# eth.net
KiCad netlist of a schematic drawn in Altium Designer
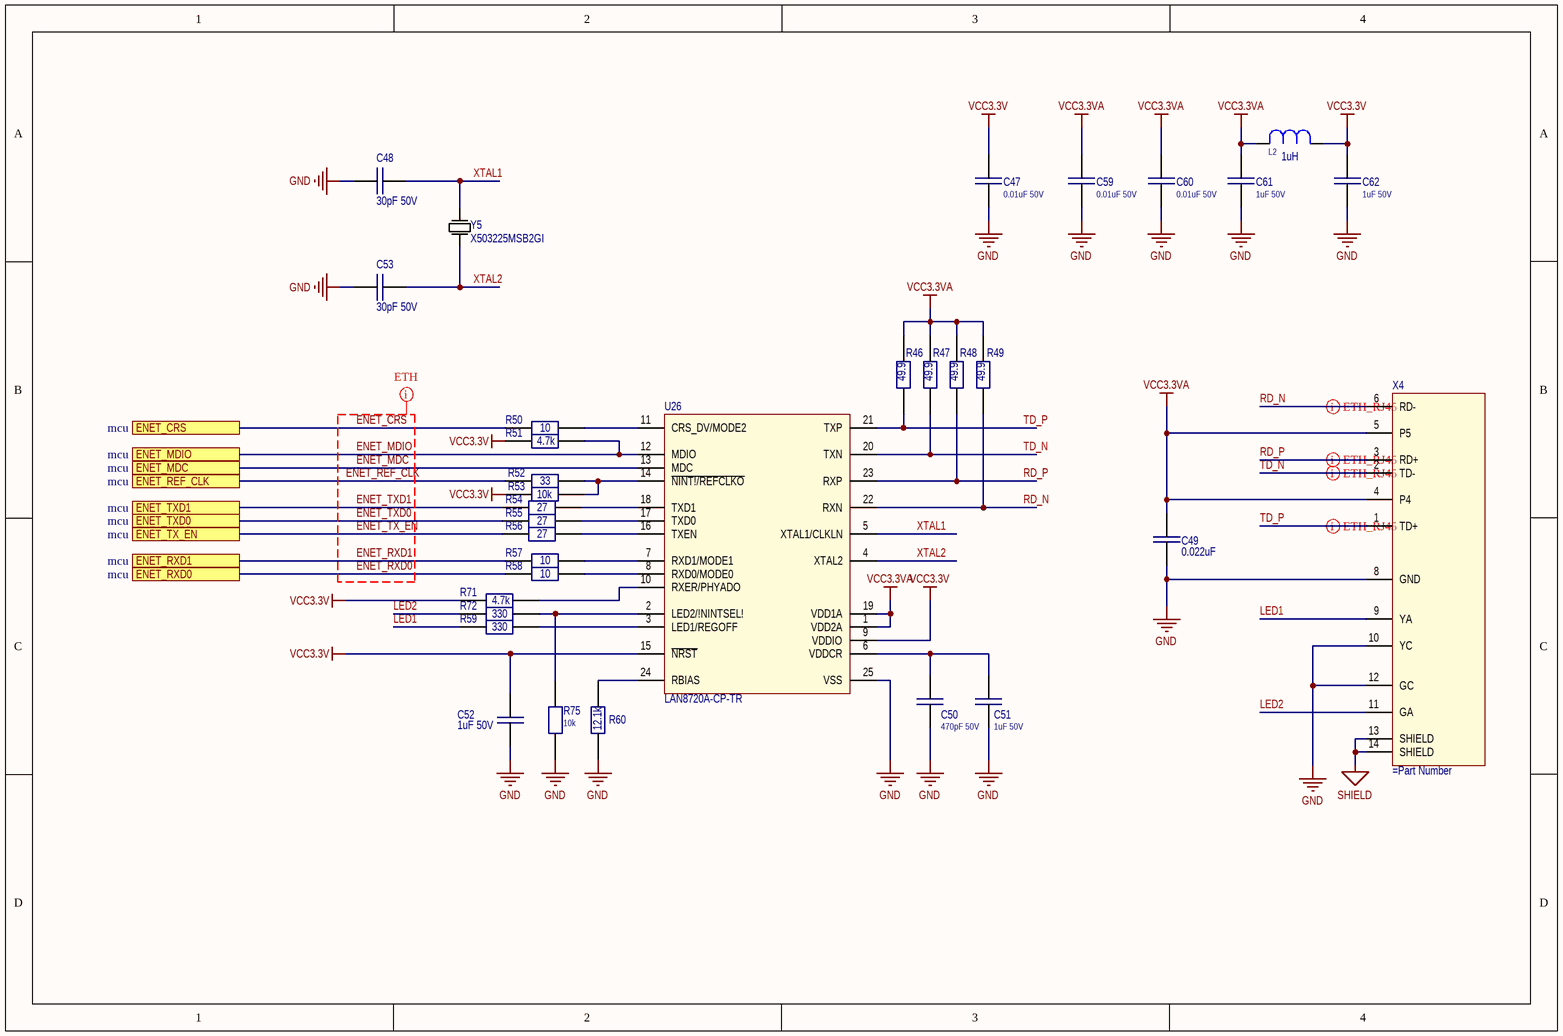
[diagram p0: eth.SchDoc]

(export (version "E")
  (design (tool "Eeschema 10.0.6"))
  (components
    (comp (ref "C47")
      (value "0.01uF 50V")
      (footprint "C_0402")
      (description "Capacitor")
      (fields (field (name "PART") "CC0402KRX7R9BB103") (field (name "JLCPCB PART") "C60133"))
      (libsource (lib "capacitors") (part "C0402"))
    )
    (comp (ref "C48")
      (value "30pF 50V")
      (footprint "C_0603")
      (description "Capacitor")
      (fields (field (name "PART") "CC0603JRNPO9BN300") (field (name "JLCPCB PART") "C113797"))
      (libsource (lib "capacitors") (part "CAP_SMD"))
    )
    (comp (ref "C49")
      (value "0.022uF")
      (footprint "C_0603")
      (description "Capacitor")
      (fields (field (name "PART") "CC0603KRX7R9BB223") (field (name "JLCPCB PART") "C106222"))
      (libsource (lib "capacitors") (part "CAP_SMD"))
    )
    (comp (ref "C50")
      (value "470pF 50V")
      (footprint "C_0402")
      (description "Capacitor")
      (fields (field (name "PART") "CC0402KRX7R9BB471") (field (name "JLCPCB PART") "C106207"))
      (libsource (lib "capacitors") (part "C0402"))
    )
    (comp (ref "C51")
      (value "1uF 50V")
      (footprint "C_0603")
      (description "Capacitor")
      (fields (field (name "PART") "CC0603KRX7R9BB105") (field (name "JLCPCB PART") "C559769"))
      (libsource (lib "capacitors") (part "CAP_SMD"))
    )
    (comp (ref "C52")
      (value "1uF 50V")
      (footprint "C_0603")
      (description "Capacitor")
      (fields (field (name "PART") "CC0603KRX7R9BB105") (field (name "JLCPCB PART") "C559769"))
      (libsource (lib "capacitors") (part "CAP_SMD"))
    )
    (comp (ref "C53")
      (value "30pF 50V")
      (footprint "C_0603")
      (description "Capacitor")
      (fields (field (name "PART") "CC0603JRNPO9BN300") (field (name "JLCPCB PART") "C113797"))
      (libsource (lib "capacitors") (part "CAP_SMD"))
    )
    (comp (ref "C59")
      (value "0.01uF 50V")
      (footprint "C_0402")
      (description "Capacitor")
      (fields (field (name "PART") "CC0402KRX7R9BB103") (field (name "JLCPCB PART") "C60133"))
      (libsource (lib "capacitors") (part "C0402"))
    )
    (comp (ref "C60")
      (value "0.01uF 50V")
      (footprint "C_0402")
      (description "Capacitor")
      (fields (field (name "PART") "CC0402KRX7R9BB103") (field (name "JLCPCB PART") "C60133"))
      (libsource (lib "capacitors") (part "C0402"))
    )
    (comp (ref "C61")
      (value "1uF 50V")
      (footprint "C_0603")
      (description "Capacitor")
      (fields (field (name "PART") "CC0603KRX7R9BB105") (field (name "JLCPCB PART") "C559769"))
      (libsource (lib "capacitors") (part "C0603"))
    )
    (comp (ref "C62")
      (value "1uF 50V")
      (footprint "C_0603")
      (description "Capacitor")
      (fields (field (name "PART") "CC0603KRX7R9BB105") (field (name "JLCPCB PART") "C559769"))
      (libsource (lib "capacitors") (part "C0603"))
    )
    (comp (ref "L2")
      (value "1uH")
      (footprint "L_0603")
      (description "Inductor")
      (fields (field (name "PART") "LQM18FN1R0M00D") (field (name "JLCPCB PART") "C113093"))
      (libsource (lib "inductors_transformers") (part "L_0603"))
    )
    (comp (ref "R46")
      (value "49.9")
      (footprint "R_0603")
      (description "Resistor")
      (fields (field (name "PART") "RC0603FR-0749R9L") (field (name "JLCPCB PART") "C114625"))
      (libsource (lib "resistors") (part "RES_SMD"))
    )
    (comp (ref "R47")
      (value "49.9")
      (footprint "R_0603")
      (description "Resistor")
      (fields (field (name "PART") "RC0603FR-0749R9L") (field (name "JLCPCB PART") "C114625"))
      (libsource (lib "resistors") (part "RES_SMD"))
    )
    (comp (ref "R48")
      (value "49.9")
      (footprint "R_0603")
      (description "Resistor")
      (fields (field (name "PART") "RC0603FR-0749R9L") (field (name "JLCPCB PART") "C114625"))
      (libsource (lib "resistors") (part "RES_SMD"))
    )
    (comp (ref "R49")
      (value "49.9")
      (footprint "R_0603")
      (description "Resistor")
      (fields (field (name "PART") "RC0603FR-0749R9L") (field (name "JLCPCB PART") "C114625"))
      (libsource (lib "resistors") (part "RES_SMD"))
    )
    (comp (ref "R50")
      (value "10")
      (footprint "R_0603")
      (description "Resistor")
      (fields (field (name "PART") "RC0603FR-0710RL") (field (name "JLCPCB PART") "C109318"))
      (libsource (lib "resistors") (part "RES_SMD"))
    )
    (comp (ref "R51")
      (value "4.7k")
      (footprint "R_0603")
      (description "Resistor")
      (fields (field (name "PART") "RC0603FR-074K7L") (field (name "JLCPCB PART") "C99782"))
      (libsource (lib "resistors") (part "RES_SMD"))
    )
    (comp (ref "R52")
      (value "33")
      (footprint "R_0603")
      (description "Resistor")
      (fields (field (name "PART") "RC0603FR-0733RL") (field (name "JLCPCB PART") "C108661"))
      (libsource (lib "resistors") (part "RES_SMD"))
    )
    (comp (ref "R53")
      (value "10k")
      (footprint "R_0603")
      (description "Resistor")
      (fields (field (name "PART") "RC0603JR-0710KL") (field (name "JLCPCB PART") "C99198"))
      (libsource (lib "resistors") (part "RES_SMD"))
    )
    (comp (ref "R54")
      (value "27")
      (footprint "R_0603")
      (description "Resistor")
      (fields (field (name "PART") "RC0402JR-0727RL") (field (name "JLCPCB PART") "C137639"))
      (libsource (lib "resistors") (part "RES_SMD"))
    )
    (comp (ref "R55")
      (value "27")
      (footprint "R_0603")
      (description "Resistor")
      (fields (field (name "PART") "RC0402JR-0727RL") (field (name "JLCPCB PART") "C137639"))
      (libsource (lib "resistors") (part "RES_SMD"))
    )
    (comp (ref "R56")
      (value "27")
      (footprint "R_0603")
      (description "Resistor")
      (fields (field (name "PART") "RC0402JR-0727RL") (field (name "JLCPCB PART") "C137639"))
      (libsource (lib "resistors") (part "RES_SMD"))
    )
    (comp (ref "R57")
      (value "10")
      (footprint "R_0603")
      (description "Resistor")
      (fields (field (name "PART") "RC0603FR-0710RL") (field (name "JLCPCB PART") "C109318"))
      (libsource (lib "resistors") (part "RES_SMD"))
    )
    (comp (ref "R58")
      (value "10")
      (footprint "R_0603")
      (description "Resistor")
      (fields (field (name "PART") "RC0603FR-0710RL") (field (name "JLCPCB PART") "C109318"))
      (libsource (lib "resistors") (part "RES_SMD"))
    )
    (comp (ref "R59")
      (value "330")
      (footprint "R_0603")
      (description "Resistor")
      (fields (field (name "PART") "RC0603FR-07330RL") (field (name "JLCPCB PART") "C105881"))
      (libsource (lib "resistors") (part "RES_SMD"))
    )
    (comp (ref "R60")
      (value "12.1k")
      (footprint "R_0603")
      (description "Resistor")
      (fields (field (name "PART") "RC0603FR-0712K1L") (field (name "JLCPCB PART") "C123417"))
      (libsource (lib "resistors") (part "RES_SMD"))
    )
    (comp (ref "R71")
      (value "4.7k")
      (footprint "R_0603")
      (description "Resistor")
      (fields (field (name "PART") "RC0603FR-074K7L") (field (name "JLCPCB PART") "C99782"))
      (libsource (lib "resistors") (part "RES_SMD"))
    )
    (comp (ref "R72")
      (value "330")
      (footprint "R_0603")
      (description "Resistor")
      (fields (field (name "PART") "RC0603FR-07330RL") (field (name "JLCPCB PART") "C105881"))
      (libsource (lib "resistors") (part "RES_SMD"))
    )
    (comp (ref "R75")
      (value "10k")
      (footprint "R_0603")
      (description "Resistor")
      (fields (field (name "PART") "RC0603JR-0710KL") (field (name "JLCPCB PART") "C99198"))
      (libsource (lib "bmplc") (part "RES_SMD"))
    )
    (comp (ref "U26")
      (value "LAN8720A-CP-TR")
      (footprint "QFN50P400X400X100-25N")
      (description "Phy Eth 2/2 Transceiver Full RMII 24-QFN-EP _4x4_")
      (fields (field (name "MF") "Microchip") (field (name "MP") "LAN8720A-CP"))
      (libsource (lib "discret_ic") (part "LAN8720"))
    )
    (comp (ref "X4")
      (value "~")
      (footprint "RJ45-TH_HR915340A")
      (description "DIP RJ45 Connector;")
      (fields (field (name "MP") "HR915340A") (field (name "JLCPCB PART") "C2760325"))
      (libsource (lib "connectors_socets") (part "HR915340A"))
    )
    (comp (ref "Y5")
      (value "X503225MSB2GI")
      (footprint "X5032")
      (description "Crystal Oscillator")
      (fields (field (name "JLCPCB PART") "C112569"))
      (libsource (lib "crystals_oscillators") (part "X503212MSB2GI"))
    )
  )
  (nets
    (net (code "1") (name "/ENET_CRS") (class "Default")
      (node (ref "R50") (pin "1") (pinfunction "1_1") (pintype "passive"))
    )
    (net (code "2") (name "/ENET_MDC") (class "Default")
      (node (ref "U26") (pin "13") (pinfunction "MDC_13") (pintype "passive"))
    )
    (net (code "3") (name "/ENET_MDIO") (class "Default")
      (node (ref "R51") (pin "2") (pinfunction "2_2") (pintype "passive"))
      (node (ref "U26") (pin "12") (pinfunction "MDIO_12") (pintype "passive"))
    )
    (net (code "4") (name "/ENET_REF_CLK") (class "Default")
      (node (ref "R52") (pin "1") (pinfunction "1_1") (pintype "passive"))
    )
    (net (code "5") (name "/ENET_RXD0") (class "Default")
      (node (ref "R58") (pin "1") (pinfunction "1_1") (pintype "passive"))
    )
    (net (code "6") (name "/ENET_RXD1") (class "Default")
      (node (ref "R57") (pin "1") (pinfunction "1_1") (pintype "passive"))
    )
    (net (code "7") (name "/ENET_TXD0") (class "Default")
      (node (ref "R55") (pin "1") (pinfunction "1_1") (pintype "passive"))
    )
    (net (code "8") (name "/ENET_TXD1") (class "Default")
      (node (ref "R54") (pin "1") (pinfunction "1_1") (pintype "passive"))
    )
    (net (code "9") (name "/ENET_TX_EN") (class "Default")
      (node (ref "R56") (pin "1") (pinfunction "1_1") (pintype "passive"))
    )
    (net (code "10") (name "/LED1") (class "Default")
      (node (ref "R59") (pin "2") (pinfunction "2_2") (pintype "passive"))
      (node (ref "X4") (pin "9") (pinfunction "YA_9") (pintype "passive"))
    )
    (net (code "11") (name "/LED2") (class "Default")
      (node (ref "R72") (pin "2") (pinfunction "2_2") (pintype "passive"))
      (node (ref "X4") (pin "11") (pinfunction "GA_11") (pintype "passive"))
    )
    (net (code "12") (name "/RD_N") (class "Default")
      (node (ref "R49") (pin "1") (pinfunction "1_1") (pintype "passive"))
      (node (ref "U26") (pin "22") (pinfunction "RXN_22") (pintype "passive"))
      (node (ref "X4") (pin "6") (pinfunction "RD-_6") (pintype "passive"))
    )
    (net (code "13") (name "/RD_P") (class "Default")
      (node (ref "R48") (pin "1") (pinfunction "1_1") (pintype "passive"))
      (node (ref "U26") (pin "23") (pinfunction "RXP_23") (pintype "passive"))
      (node (ref "X4") (pin "3") (pinfunction "RD+_3") (pintype "passive"))
    )
    (net (code "14") (name "/TD_N") (class "Default")
      (node (ref "R47") (pin "1") (pinfunction "1_1") (pintype "passive"))
      (node (ref "U26") (pin "20") (pinfunction "TXN_20") (pintype "passive"))
      (node (ref "X4") (pin "2") (pinfunction "TD-_2") (pintype "passive"))
    )
    (net (code "15") (name "/TD_P") (class "Default")
      (node (ref "R46") (pin "1") (pinfunction "1_1") (pintype "passive"))
      (node (ref "U26") (pin "21") (pinfunction "TXP_21") (pintype "passive"))
      (node (ref "X4") (pin "1") (pinfunction "TD+_1") (pintype "passive"))
    )
    (net (code "16") (name "/XTAL1") (class "Default")
      (node (ref "C48") (pin "1") (pinfunction "1_1") (pintype "passive"))
      (node (ref "U26") (pin "5") (pinfunction "XTAL1/CLKLN_5") (pintype "passive"))
      (node (ref "Y5") (pin "1") (pinfunction "1_1") (pintype "passive"))
    )
    (net (code "17") (name "/XTAL2") (class "Default")
      (node (ref "C53") (pin "1") (pinfunction "1_1") (pintype "passive"))
      (node (ref "U26") (pin "4") (pinfunction "XTAL2_4") (pintype "passive"))
      (node (ref "Y5") (pin "2") (pinfunction "2_2") (pintype "passive"))
    )
    (net (code "18") (name "GND") (class "Default")
      (node (ref "C47") (pin "2") (pinfunction "2_2") (pintype "passive"))
      (node (ref "C48") (pin "2") (pinfunction "2_2") (pintype "passive"))
      (node (ref "C49") (pin "1") (pinfunction "1_1") (pintype "passive"))
      (node (ref "C50") (pin "2") (pinfunction "2_2") (pintype "passive"))
      (node (ref "C51") (pin "1") (pinfunction "1_1") (pintype "passive"))
      (node (ref "C52") (pin "1") (pinfunction "1_1") (pintype "passive"))
      (node (ref "C53") (pin "2") (pinfunction "2_2") (pintype "passive"))
      (node (ref "C59") (pin "2") (pinfunction "2_2") (pintype "passive"))
      (node (ref "C60") (pin "2") (pinfunction "2_2") (pintype "passive"))
      (node (ref "C61") (pin "1") (pinfunction "1_1") (pintype "passive"))
      (node (ref "C62") (pin "1") (pinfunction "1_1") (pintype "passive"))
      (node (ref "R60") (pin "1") (pinfunction "1_1") (pintype "passive"))
      (node (ref "R75") (pin "1") (pinfunction "1_1") (pintype "passive"))
      (node (ref "U26") (pin "25") (pinfunction "VSS_25") (pintype "passive"))
      (node (ref "X4") (pin "10") (pinfunction "YC_10") (pintype "passive"))
      (node (ref "X4") (pin "12") (pinfunction "GC_12") (pintype "passive"))
      (node (ref "X4") (pin "8") (pinfunction "GND_8") (pintype "power_in"))
    )
    (net (code "19") (name "Net-(U26-CRS_DV{slash}MODE2)") (class "Default")
      (node (ref "R50") (pin "2") (pinfunction "2_2") (pintype "passive"))
      (node (ref "U26") (pin "11") (pinfunction "CRS_DV/MODE2_11") (pintype "passive"))
    )
    (net (code "20") (name "Net-(U26-LED1{slash}REGOFF)") (class "Default")
      (node (ref "R59") (pin "1") (pinfunction "1_1") (pintype "passive"))
      (node (ref "U26") (pin "3") (pinfunction "LED1/REGOFF_3") (pintype "passive"))
    )
    (net (code "21") (name "Net-(U26-LED2{slash}!NINTSEL!)") (class "Default")
      (node (ref "R72") (pin "1") (pinfunction "1_1") (pintype "passive"))
      (node (ref "R75") (pin "2") (pinfunction "2_2") (pintype "passive"))
      (node (ref "U26") (pin "2") (pinfunction "LED2/!NINTSEL!_2") (pintype "passive"))
    )
    (net (code "22") (name "Net-(U26-RBIAS)") (class "Default")
      (node (ref "R60") (pin "2") (pinfunction "2_2") (pintype "passive"))
      (node (ref "U26") (pin "24") (pinfunction "RBIAS_24") (pintype "passive"))
    )
    (net (code "23") (name "Net-(U26-RXD0{slash}MODE0)") (class "Default")
      (node (ref "R58") (pin "2") (pinfunction "2_2") (pintype "passive"))
      (node (ref "U26") (pin "8") (pinfunction "RXD0/MODE0_8") (pintype "passive"))
    )
    (net (code "24") (name "Net-(U26-RXD1{slash}MODE1)") (class "Default")
      (node (ref "R57") (pin "2") (pinfunction "2_2") (pintype "passive"))
      (node (ref "U26") (pin "7") (pinfunction "RXD1/MODE1_7") (pintype "passive"))
    )
    (net (code "25") (name "Net-(U26-RXER{slash}PHYADO)") (class "Default")
      (node (ref "R71") (pin "2") (pinfunction "2_2") (pintype "passive"))
      (node (ref "U26") (pin "10") (pinfunction "RXER/PHYADO_10") (pintype "passive"))
    )
    (net (code "26") (name "Net-(U26-TXD0)") (class "Default")
      (node (ref "R55") (pin "2") (pinfunction "2_2") (pintype "passive"))
      (node (ref "U26") (pin "17") (pinfunction "TXD0_17") (pintype "passive"))
    )
    (net (code "27") (name "Net-(U26-TXD1)") (class "Default")
      (node (ref "R54") (pin "2") (pinfunction "2_2") (pintype "passive"))
      (node (ref "U26") (pin "18") (pinfunction "TXD1_18") (pintype "passive"))
    )
    (net (code "28") (name "Net-(U26-TXEN)") (class "Default")
      (node (ref "R56") (pin "2") (pinfunction "2_2") (pintype "passive"))
      (node (ref "U26") (pin "16") (pinfunction "TXEN_16") (pintype "passive"))
    )
    (net (code "29") (name "Net-(U26-VDDCR)") (class "Default")
      (node (ref "C50") (pin "1") (pinfunction "1_1") (pintype "passive"))
      (node (ref "C51") (pin "2") (pinfunction "2_2") (pintype "passive"))
      (node (ref "U26") (pin "6") (pinfunction "VDDCR_6") (pintype "passive"))
    )
    (net (code "30") (name "Net-(U26-~{NINT!{slash}REFCLKO})") (class "Default")
      (node (ref "R52") (pin "2") (pinfunction "2_2") (pintype "passive"))
      (node (ref "R53") (pin "1") (pinfunction "1_1") (pintype "passive"))
      (node (ref "U26") (pin "14") (pinfunction "~{NINT!/REFCLKO}_14") (pintype "passive"))
    )
    (net (code "31") (name "SHIELD") (class "Default")
      (node (ref "X4") (pin "13") (pinfunction "SHIELD_13") (pintype "passive"))
      (node (ref "X4") (pin "14") (pinfunction "SHIELD_14") (pintype "passive"))
    )
    (net (code "32") (name "VCC3.3V") (class "Default")
      (node (ref "C47") (pin "1") (pinfunction "1_1") (pintype "passive"))
      (node (ref "C52") (pin "2") (pinfunction "2_2") (pintype "passive"))
      (node (ref "C62") (pin "2") (pinfunction "2_2") (pintype "passive"))
      (node (ref "L2") (pin "2") (pintype "passive"))
      (node (ref "R51") (pin "1") (pinfunction "1_1") (pintype "passive"))
      (node (ref "R53") (pin "2") (pinfunction "2_2") (pintype "passive"))
      (node (ref "R71") (pin "1") (pinfunction "1_1") (pintype "passive"))
      (node (ref "U26") (pin "15") (pinfunction "~{NRST}_15") (pintype "passive"))
      (node (ref "U26") (pin "9") (pinfunction "VDDIO_9") (pintype "passive"))
    )
    (net (code "33") (name "VCC3.3VA") (class "Default")
      (node (ref "C49") (pin "2") (pinfunction "2_2") (pintype "passive"))
      (node (ref "C59") (pin "1") (pinfunction "1_1") (pintype "passive"))
      (node (ref "C60") (pin "1") (pinfunction "1_1") (pintype "passive"))
      (node (ref "C61") (pin "2") (pinfunction "2_2") (pintype "passive"))
      (node (ref "L2") (pin "1") (pintype "passive"))
      (node (ref "R46") (pin "2") (pinfunction "2_2") (pintype "passive"))
      (node (ref "R47") (pin "2") (pinfunction "2_2") (pintype "passive"))
      (node (ref "R48") (pin "2") (pinfunction "2_2") (pintype "passive"))
      (node (ref "R49") (pin "2") (pinfunction "2_2") (pintype "passive"))
      (node (ref "U26") (pin "1") (pinfunction "VDD2A_1") (pintype "passive"))
      (node (ref "U26") (pin "19") (pinfunction "VDD1A_19") (pintype "passive"))
      (node (ref "X4") (pin "4") (pinfunction "P4_4") (pintype "passive"))
      (node (ref "X4") (pin "5") (pinfunction "P5_5") (pintype "passive"))
    )
  )
)
